# anemo2.net
KiCad netlist of a schematic drawn in EAGLE
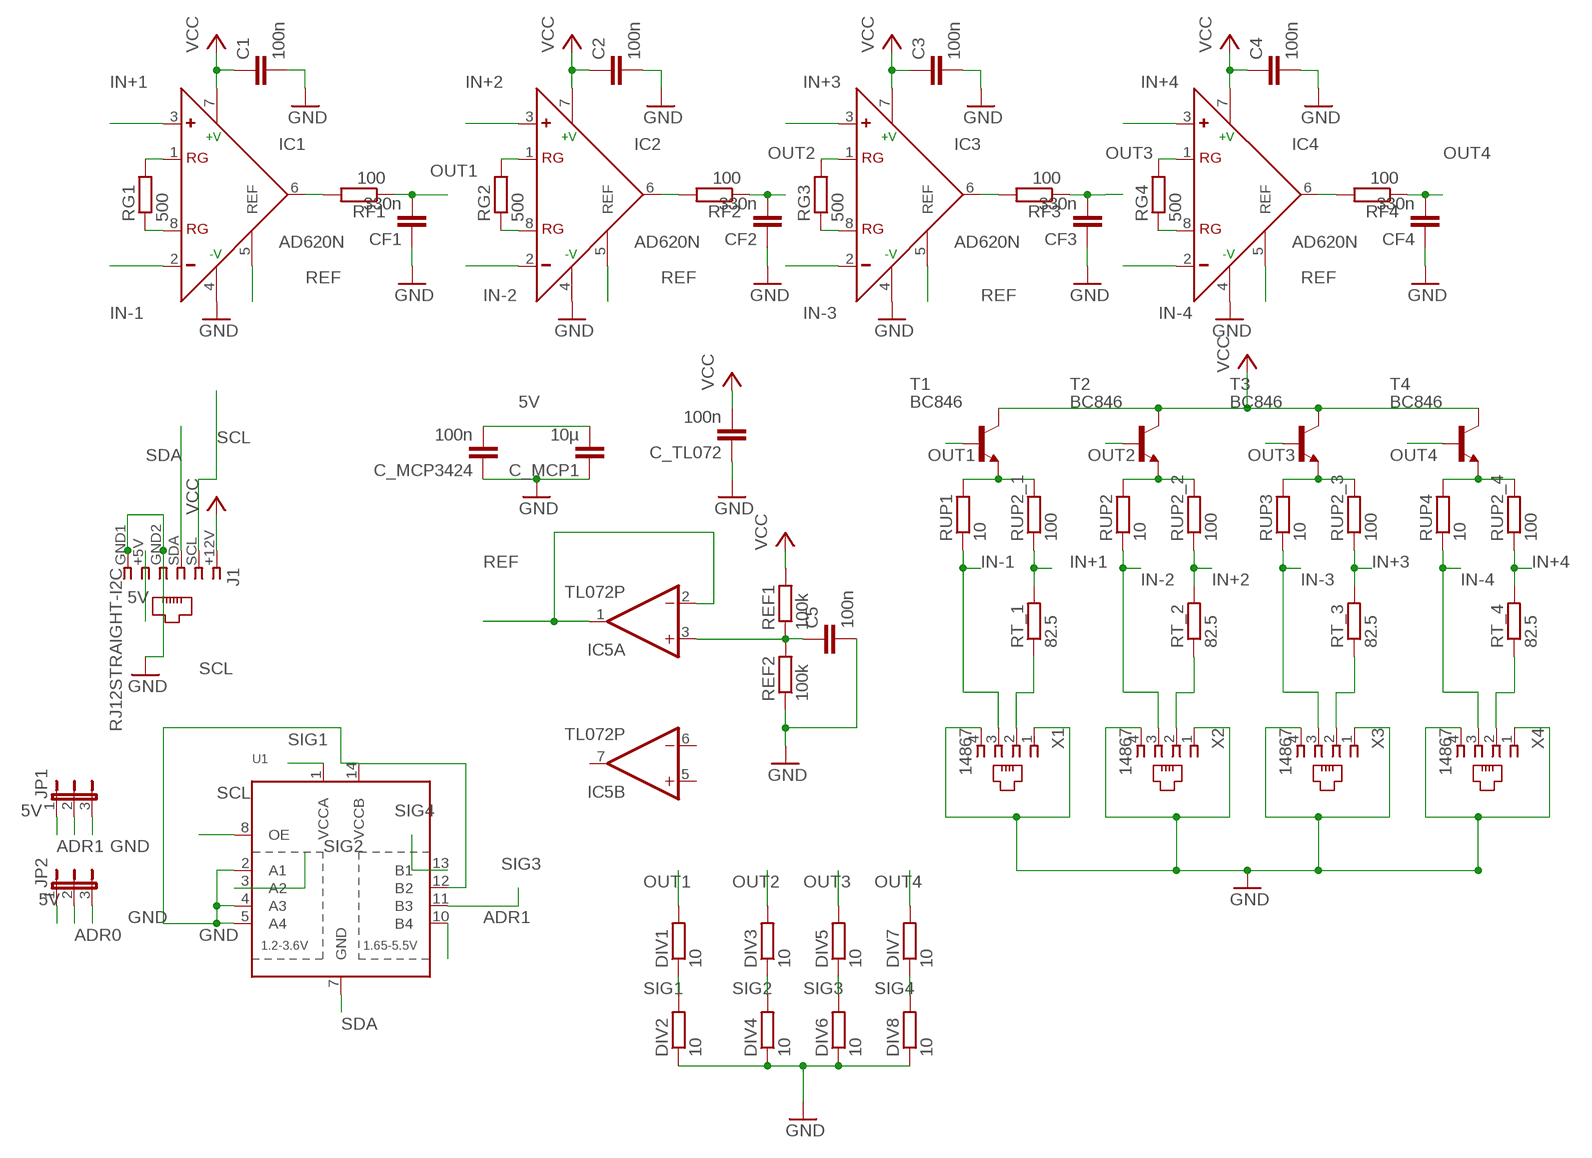
[diagram p0: schematic, sheet 1]

(export (version "E")
  (design (tool "Eeschema 10.0.6"))
  (components
    (comp (ref "C1")
      (value "100n")
      (footprint "eagle-import:C1206")
      (libsource (lib "eagle-import") (part "C-EUC1206"))
    )
    (comp (ref "C2")
      (value "100n")
      (footprint "eagle-import:C1206")
      (libsource (lib "eagle-import") (part "C-EUC1206"))
    )
    (comp (ref "C3")
      (value "100n")
      (footprint "eagle-import:C1206")
      (libsource (lib "eagle-import") (part "C-EUC1206"))
    )
    (comp (ref "C4")
      (value "100n")
      (footprint "eagle-import:C1206")
      (libsource (lib "eagle-import") (part "C-EUC1206"))
    )
    (comp (ref "C5")
      (value "100n")
      (footprint "eagle-import:C1206")
      (libsource (lib "eagle-import") (part "C-EUC1206"))
    )
    (comp (ref "CF1")
      (value "330n")
      (footprint "eagle-import:C1206")
      (libsource (lib "eagle-import") (part "C-EUC1206"))
    )
    (comp (ref "CF2")
      (value "330n")
      (footprint "eagle-import:C1206")
      (libsource (lib "eagle-import") (part "C-EUC1206"))
    )
    (comp (ref "CF3")
      (value "330n")
      (footprint "eagle-import:C1206")
      (libsource (lib "eagle-import") (part "C-EUC1206"))
    )
    (comp (ref "CF4")
      (value "330n")
      (footprint "eagle-import:C1206")
      (libsource (lib "eagle-import") (part "C-EUC1206"))
    )
    (comp (ref "C_MCP1")
      (value "10µ")
      (footprint "eagle-import:C1206")
      (libsource (lib "eagle-import") (part "C-EUC1206"))
    )
    (comp (ref "C_MCP3424")
      (value "100n")
      (footprint "eagle-import:C1206")
      (libsource (lib "eagle-import") (part "C-EUC1206"))
    )
    (comp (ref "C_TL072")
      (value "100n")
      (footprint "eagle-import:C1206")
      (libsource (lib "eagle-import") (part "C-EUC1206"))
    )
    (comp (ref "DIV1")
      (value "10")
      (footprint "eagle-import:M1206")
      (libsource (lib "eagle-import") (part "R-EU_M1206"))
    )
    (comp (ref "DIV2")
      (value "10")
      (footprint "eagle-import:M1206")
      (libsource (lib "eagle-import") (part "R-EU_M1206"))
    )
    (comp (ref "DIV3")
      (value "10")
      (footprint "eagle-import:M1206")
      (libsource (lib "eagle-import") (part "R-EU_M1206"))
    )
    (comp (ref "DIV4")
      (value "10")
      (footprint "eagle-import:M1206")
      (libsource (lib "eagle-import") (part "R-EU_M1206"))
    )
    (comp (ref "DIV5")
      (value "10")
      (footprint "eagle-import:M1206")
      (libsource (lib "eagle-import") (part "R-EU_M1206"))
    )
    (comp (ref "DIV6")
      (value "10")
      (footprint "eagle-import:M1206")
      (libsource (lib "eagle-import") (part "R-EU_M1206"))
    )
    (comp (ref "DIV7")
      (value "10")
      (footprint "eagle-import:M1206")
      (libsource (lib "eagle-import") (part "R-EU_M1206"))
    )
    (comp (ref "DIV8")
      (value "10")
      (footprint "eagle-import:M1206")
      (libsource (lib "eagle-import") (part "R-EU_M1206"))
    )
    (comp (ref "IC1")
      (value "AD620N")
      (footprint "eagle-import:DIL08")
      (fields (field (name "MF") "ALTERA CORPORATION") (field (name "MPN") "AD620AN"))
      (libsource (lib "eagle-import") (part "AD620N"))
    )
    (comp (ref "IC2")
      (value "AD620N")
      (footprint "eagle-import:DIL08")
      (fields (field (name "MF") "ALTERA CORPORATION") (field (name "MPN") "AD620AN"))
      (libsource (lib "eagle-import") (part "AD620N"))
    )
    (comp (ref "IC3")
      (value "AD620N")
      (footprint "eagle-import:DIL08")
      (fields (field (name "MF") "ALTERA CORPORATION") (field (name "MPN") "AD620AN"))
      (libsource (lib "eagle-import") (part "AD620N"))
    )
    (comp (ref "IC4")
      (value "AD620N")
      (footprint "eagle-import:DIL08")
      (fields (field (name "MF") "ALTERA CORPORATION") (field (name "MPN") "AD620AN"))
      (libsource (lib "eagle-import") (part "AD620N"))
    )
    (comp (ref "IC5")
      (value "TL072P")
      (footprint "eagle-import:DIL08")
      (libsource (lib "eagle-import") (part "TL072P"))
    )
    (comp (ref "J1")
      (value "RJ12STRAIGHT-I2C")
      (footprint "eagle-import:RJ12-STRAIGHT-I2C")
      (libsource (lib "eagle-import") (part "RJ12STRAIGHT-I2C"))
    )
    (comp (ref "JP1")
      (value "JP2E")
      (footprint "eagle-import:JP2")
      (libsource (lib "eagle-import") (part "JP2E"))
    )
    (comp (ref "JP2")
      (value "JP2E")
      (footprint "eagle-import:JP2")
      (libsource (lib "eagle-import") (part "JP2E"))
    )
    (comp (ref "REF1")
      (value "100k")
      (footprint "eagle-import:M1206")
      (libsource (lib "eagle-import") (part "R-EU_M1206"))
    )
    (comp (ref "REF2")
      (value "100k")
      (footprint "eagle-import:M1206")
      (libsource (lib "eagle-import") (part "R-EU_M1206"))
    )
    (comp (ref "RF1")
      (value "100")
      (footprint "eagle-import:M1206")
      (libsource (lib "eagle-import") (part "R-EU_M1206"))
    )
    (comp (ref "RF2")
      (value "100")
      (footprint "eagle-import:M1206")
      (libsource (lib "eagle-import") (part "R-EU_M1206"))
    )
    (comp (ref "RF3")
      (value "100")
      (footprint "eagle-import:M1206")
      (libsource (lib "eagle-import") (part "R-EU_M1206"))
    )
    (comp (ref "RF4")
      (value "100")
      (footprint "eagle-import:M1206")
      (libsource (lib "eagle-import") (part "R-EU_M1206"))
    )
    (comp (ref "RG1")
      (value "500")
      (footprint "eagle-import:M1206")
      (libsource (lib "eagle-import") (part "R-EU_M1206"))
    )
    (comp (ref "RG2")
      (value "500")
      (footprint "eagle-import:M1206")
      (libsource (lib "eagle-import") (part "R-EU_M1206"))
    )
    (comp (ref "RG3")
      (value "500")
      (footprint "eagle-import:M1206")
      (libsource (lib "eagle-import") (part "R-EU_M1206"))
    )
    (comp (ref "RG4")
      (value "500")
      (footprint "eagle-import:M1206")
      (libsource (lib "eagle-import") (part "R-EU_M1206"))
    )
    (comp (ref "RT_1")
      (value "82.5")
      (footprint "eagle-import:M1206")
      (libsource (lib "eagle-import") (part "R-EU_M1206"))
    )
    (comp (ref "RT_2")
      (value "82.5")
      (footprint "eagle-import:M1206")
      (libsource (lib "eagle-import") (part "R-EU_M1206"))
    )
    (comp (ref "RT_3")
      (value "82.5")
      (footprint "eagle-import:M1206")
      (libsource (lib "eagle-import") (part "R-EU_M1206"))
    )
    (comp (ref "RT_4")
      (value "82.5")
      (footprint "eagle-import:M1206")
      (libsource (lib "eagle-import") (part "R-EU_M1206"))
    )
    (comp (ref "RUP1")
      (value "10")
      (footprint "eagle-import:M1206")
      (libsource (lib "eagle-import") (part "R-EU_M1206"))
    )
    (comp (ref "RUP2")
      (value "10")
      (footprint "eagle-import:M1206")
      (libsource (lib "eagle-import") (part "R-EU_M1206"))
    )
    (comp (ref "RUP2_1")
      (value "100")
      (footprint "eagle-import:M1206")
      (libsource (lib "eagle-import") (part "R-EU_M1206"))
    )
    (comp (ref "RUP2_2")
      (value "100")
      (footprint "eagle-import:M1206")
      (libsource (lib "eagle-import") (part "R-EU_M1206"))
    )
    (comp (ref "RUP2_3")
      (value "100")
      (footprint "eagle-import:M1206")
      (libsource (lib "eagle-import") (part "R-EU_M1206"))
    )
    (comp (ref "RUP2_4")
      (value "100")
      (footprint "eagle-import:M1206")
      (libsource (lib "eagle-import") (part "R-EU_M1206"))
    )
    (comp (ref "RUP3")
      (value "10")
      (footprint "eagle-import:M1206")
      (libsource (lib "eagle-import") (part "R-EU_M1206"))
    )
    (comp (ref "RUP4")
      (value "10")
      (footprint "eagle-import:M1206")
      (libsource (lib "eagle-import") (part "R-EU_M1206"))
    )
    (comp (ref "T1")
      (value "BC846")
      (footprint "eagle-import:SOT23")
      (libsource (lib "eagle-import") (part "BC846"))
    )
    (comp (ref "T2")
      (value "BC846")
      (footprint "eagle-import:SOT23")
      (libsource (lib "eagle-import") (part "BC846"))
    )
    (comp (ref "T3")
      (value "BC846")
      (footprint "eagle-import:SOT23")
      (libsource (lib "eagle-import") (part "BC846"))
    )
    (comp (ref "T4")
      (value "BC846")
      (footprint "eagle-import:SOT23")
      (libsource (lib "eagle-import") (part "BC846"))
    )
    (comp (ref "U1")
      (value "TXB0104PWRSOIC14")
      (footprint "eagle-import:SO14")
      (libsource (lib "eagle-import") (part "TXB0104PWRSOIC14"))
    )
    (comp (ref "X1")
      (value "14867")
      (footprint "eagle-import:14867")
      (libsource (lib "eagle-import") (part "14867"))
    )
    (comp (ref "X2")
      (value "14867")
      (footprint "eagle-import:14867")
      (libsource (lib "eagle-import") (part "14867"))
    )
    (comp (ref "X3")
      (value "14867")
      (footprint "eagle-import:14867")
      (libsource (lib "eagle-import") (part "14867"))
    )
    (comp (ref "X4")
      (value "14867")
      (footprint "eagle-import:14867")
      (libsource (lib "eagle-import") (part "14867"))
    )
  )
  (nets
    (net (code "1") (name "/5V") (class "Default")
      (node (ref "C_MCP1") (pin "2") (pinfunction "2_2") (pintype "passive"))
      (node (ref "C_MCP3424") (pin "2") (pinfunction "2_2") (pintype "passive"))
      (node (ref "J1") (pin "+5V") (pinfunction "5_+5V") (pintype "bidirectional"))
      (node (ref "JP1") (pin "1") (pinfunction "1_1") (pintype "passive"))
      (node (ref "JP2") (pin "1") (pinfunction "1_1") (pintype "passive"))
    )
    (net (code "2") (name "/ADR0") (class "Default")
      (node (ref "JP2") (pin "2") (pinfunction "2_2") (pintype "passive"))
    )
    (net (code "3") (name "/ADR1") (class "Default")
      (node (ref "JP1") (pin "2") (pinfunction "2_2") (pintype "passive"))
      (node (ref "U1") (pin "10") (pinfunction "B4_10") (pintype "bidirectional"))
    )
    (net (code "4") (name "/IN+1") (class "Default")
      (node (ref "IC1") (pin "3") (pinfunction "+_3") (pintype "input"))
      (node (ref "RT_1") (pin "2") (pinfunction "2_2") (pintype "passive"))
      (node (ref "RUP2_1") (pin "1") (pinfunction "1_1") (pintype "passive"))
    )
    (net (code "5") (name "/IN+2") (class "Default")
      (node (ref "IC2") (pin "3") (pinfunction "+_3") (pintype "input"))
      (node (ref "RT_2") (pin "2") (pinfunction "2_2") (pintype "passive"))
      (node (ref "RUP2_2") (pin "1") (pinfunction "1_1") (pintype "passive"))
    )
    (net (code "6") (name "/IN+3") (class "Default")
      (node (ref "IC3") (pin "3") (pinfunction "+_3") (pintype "input"))
      (node (ref "RT_3") (pin "2") (pinfunction "2_2") (pintype "passive"))
      (node (ref "RUP2_3") (pin "1") (pinfunction "1_1") (pintype "passive"))
    )
    (net (code "7") (name "/IN+4") (class "Default")
      (node (ref "IC4") (pin "3") (pinfunction "+_3") (pintype "input"))
      (node (ref "RT_4") (pin "2") (pinfunction "2_2") (pintype "passive"))
      (node (ref "RUP2_4") (pin "1") (pinfunction "1_1") (pintype "passive"))
    )
    (net (code "8") (name "/IN-1") (class "Default")
      (node (ref "IC1") (pin "2") (pinfunction "-_2") (pintype "input"))
      (node (ref "RUP1") (pin "1") (pinfunction "1_1") (pintype "passive"))
      (node (ref "X1") (pin "3") (pinfunction "3_3") (pintype "passive"))
    )
    (net (code "9") (name "/IN-2") (class "Default")
      (node (ref "IC2") (pin "2") (pinfunction "-_2") (pintype "input"))
      (node (ref "RUP2") (pin "1") (pinfunction "1_1") (pintype "passive"))
      (node (ref "X2") (pin "3") (pinfunction "3_3") (pintype "passive"))
    )
    (net (code "10") (name "/IN-3") (class "Default")
      (node (ref "IC3") (pin "2") (pinfunction "-_2") (pintype "input"))
      (node (ref "RUP3") (pin "1") (pinfunction "1_1") (pintype "passive"))
      (node (ref "X3") (pin "3") (pinfunction "3_3") (pintype "passive"))
    )
    (net (code "11") (name "/IN-4") (class "Default")
      (node (ref "IC4") (pin "2") (pinfunction "-_2") (pintype "input"))
      (node (ref "RUP4") (pin "1") (pinfunction "1_1") (pintype "passive"))
      (node (ref "X4") (pin "3") (pinfunction "3_3") (pintype "passive"))
    )
    (net (code "12") (name "/OUT1") (class "Default")
      (node (ref "CF1") (pin "2") (pinfunction "2_2") (pintype "passive"))
      (node (ref "DIV1") (pin "2") (pinfunction "2_2") (pintype "passive"))
      (node (ref "RF1") (pin "1") (pinfunction "1_1") (pintype "passive"))
      (node (ref "T1") (pin "1") (pinfunction "B_1") (pintype "passive"))
    )
    (net (code "13") (name "/OUT2") (class "Default")
      (node (ref "CF2") (pin "2") (pinfunction "2_2") (pintype "passive"))
      (node (ref "DIV3") (pin "2") (pinfunction "2_2") (pintype "passive"))
      (node (ref "RF2") (pin "1") (pinfunction "1_1") (pintype "passive"))
      (node (ref "T2") (pin "1") (pinfunction "B_1") (pintype "passive"))
    )
    (net (code "14") (name "/OUT3") (class "Default")
      (node (ref "CF3") (pin "2") (pinfunction "2_2") (pintype "passive"))
      (node (ref "DIV5") (pin "2") (pinfunction "2_2") (pintype "passive"))
      (node (ref "RF3") (pin "1") (pinfunction "1_1") (pintype "passive"))
      (node (ref "T3") (pin "1") (pinfunction "B_1") (pintype "passive"))
    )
    (net (code "15") (name "/OUT4") (class "Default")
      (node (ref "CF4") (pin "2") (pinfunction "2_2") (pintype "passive"))
      (node (ref "DIV7") (pin "2") (pinfunction "2_2") (pintype "passive"))
      (node (ref "RF4") (pin "1") (pinfunction "1_1") (pintype "passive"))
      (node (ref "T4") (pin "1") (pinfunction "B_1") (pintype "passive"))
    )
    (net (code "16") (name "/REF") (class "Default")
      (node (ref "IC1") (pin "5") (pinfunction "REF_5") (pintype "passive"))
      (node (ref "IC2") (pin "5") (pinfunction "REF_5") (pintype "passive"))
      (node (ref "IC3") (pin "5") (pinfunction "REF_5") (pintype "passive"))
      (node (ref "IC4") (pin "5") (pinfunction "REF_5") (pintype "passive"))
      (node (ref "IC5") (pin "1") (pinfunction "OUT_1") (pintype "output"))
      (node (ref "IC5") (pin "2") (pinfunction "-IN_2") (pintype "input"))
    )
    (net (code "17") (name "/SCL") (class "Default")
      (node (ref "J1") (pin "SCL") (pinfunction "2_SCL") (pintype "bidirectional"))
      (node (ref "U1") (pin "8") (pinfunction "OE_8") (pintype "bidirectional"))
    )
    (net (code "18") (name "/SDA") (class "Default")
      (node (ref "J1") (pin "SDA") (pinfunction "3_SDA") (pintype "bidirectional"))
      (node (ref "U1") (pin "7") (pinfunction "GND_7") (pintype "bidirectional"))
    )
    (net (code "19") (name "/SIG1") (class "Default")
      (node (ref "DIV1") (pin "1") (pinfunction "1_1") (pintype "passive"))
      (node (ref "DIV2") (pin "2") (pinfunction "2_2") (pintype "passive"))
      (node (ref "U1") (pin "1") (pinfunction "VCCA_1") (pintype "bidirectional"))
    )
    (net (code "20") (name "/SIG2") (class "Default")
      (node (ref "DIV3") (pin "1") (pinfunction "1_1") (pintype "passive"))
      (node (ref "DIV4") (pin "2") (pinfunction "2_2") (pintype "passive"))
      (node (ref "U1") (pin "3") (pinfunction "A2_3") (pintype "bidirectional"))
    )
    (net (code "21") (name "/SIG3") (class "Default")
      (node (ref "DIV5") (pin "1") (pinfunction "1_1") (pintype "passive"))
      (node (ref "DIV6") (pin "2") (pinfunction "2_2") (pintype "passive"))
      (node (ref "U1") (pin "11") (pinfunction "B3_11") (pintype "bidirectional"))
    )
    (net (code "22") (name "/SIG4") (class "Default")
      (node (ref "DIV7") (pin "1") (pinfunction "1_1") (pintype "passive"))
      (node (ref "DIV8") (pin "2") (pinfunction "2_2") (pintype "passive"))
      (node (ref "U1") (pin "13") (pinfunction "B1_13") (pintype "bidirectional"))
    )
    (net (code "23") (name "GND") (class "Default")
      (node (ref "C1") (pin "2") (pinfunction "2_2") (pintype "passive"))
      (node (ref "C2") (pin "2") (pinfunction "2_2") (pintype "passive"))
      (node (ref "C3") (pin "2") (pinfunction "2_2") (pintype "passive"))
      (node (ref "C4") (pin "2") (pinfunction "2_2") (pintype "passive"))
      (node (ref "C5") (pin "2") (pinfunction "2_2") (pintype "passive"))
      (node (ref "CF1") (pin "1") (pinfunction "1_1") (pintype "passive"))
      (node (ref "CF2") (pin "1") (pinfunction "1_1") (pintype "passive"))
      (node (ref "CF3") (pin "1") (pinfunction "1_1") (pintype "passive"))
      (node (ref "CF4") (pin "1") (pinfunction "1_1") (pintype "passive"))
      (node (ref "C_MCP1") (pin "1") (pinfunction "1_1") (pintype "passive"))
      (node (ref "C_MCP3424") (pin "1") (pinfunction "1_1") (pintype "passive"))
      (node (ref "C_TL072") (pin "1") (pinfunction "1_1") (pintype "passive"))
      (node (ref "DIV2") (pin "1") (pinfunction "1_1") (pintype "passive"))
      (node (ref "DIV4") (pin "1") (pinfunction "1_1") (pintype "passive"))
      (node (ref "DIV6") (pin "1") (pinfunction "1_1") (pintype "passive"))
      (node (ref "DIV8") (pin "1") (pinfunction "1_1") (pintype "passive"))
      (node (ref "IC1") (pin "4") (pinfunction "-V_4") (pintype "power_in"))
      (node (ref "IC2") (pin "4") (pinfunction "-V_4") (pintype "power_in"))
      (node (ref "IC3") (pin "4") (pinfunction "-V_4") (pintype "power_in"))
      (node (ref "IC4") (pin "4") (pinfunction "-V_4") (pintype "power_in"))
      (node (ref "J1") (pin "GND1") (pinfunction "6_GND1") (pintype "bidirectional"))
      (node (ref "J1") (pin "GND2") (pinfunction "4_GND2") (pintype "bidirectional"))
      (node (ref "JP1") (pin "3") (pinfunction "3_3") (pintype "passive"))
      (node (ref "JP2") (pin "3") (pinfunction "3_3") (pintype "passive"))
      (node (ref "REF2") (pin "1") (pinfunction "1_1") (pintype "passive"))
      (node (ref "U1") (pin "12") (pinfunction "B2_12") (pintype "bidirectional"))
      (node (ref "U1") (pin "14") (pinfunction "VCCB_14") (pintype "bidirectional"))
      (node (ref "U1") (pin "2") (pinfunction "A1_2") (pintype "bidirectional"))
      (node (ref "U1") (pin "4") (pinfunction "A3_4") (pintype "bidirectional"))
      (node (ref "U1") (pin "5") (pinfunction "A4_5") (pintype "bidirectional"))
      (node (ref "X1") (pin "1") (pinfunction "1_1") (pintype "passive"))
      (node (ref "X1") (pin "4") (pinfunction "4_4") (pintype "passive"))
      (node (ref "X2") (pin "1") (pinfunction "1_1") (pintype "passive"))
      (node (ref "X2") (pin "4") (pinfunction "4_4") (pintype "passive"))
      (node (ref "X3") (pin "1") (pinfunction "1_1") (pintype "passive"))
      (node (ref "X3") (pin "4") (pinfunction "4_4") (pintype "passive"))
      (node (ref "X4") (pin "1") (pinfunction "1_1") (pintype "passive"))
      (node (ref "X4") (pin "4") (pinfunction "4_4") (pintype "passive"))
    )
    (net (code "24") (name "Net-(IC1-OUT)") (class "Default")
      (node (ref "IC1") (pin "6") (pinfunction "OUT_6") (pintype "output"))
      (node (ref "RF1") (pin "2") (pinfunction "2_2") (pintype "passive"))
    )
    (net (code "25") (name "Net-(IC1-RG-Pad1)") (class "Default")
      (node (ref "IC1") (pin "1") (pinfunction "RG_1") (pintype "passive"))
      (node (ref "RG1") (pin "2") (pinfunction "2_2") (pintype "passive"))
    )
    (net (code "26") (name "Net-(IC1-RG-Pad8)") (class "Default")
      (node (ref "IC1") (pin "8") (pinfunction "RG_8") (pintype "passive"))
      (node (ref "RG1") (pin "1") (pinfunction "1_1") (pintype "passive"))
    )
    (net (code "27") (name "Net-(IC2-OUT)") (class "Default")
      (node (ref "IC2") (pin "6") (pinfunction "OUT_6") (pintype "output"))
      (node (ref "RF2") (pin "2") (pinfunction "2_2") (pintype "passive"))
    )
    (net (code "28") (name "Net-(IC2-RG-Pad1)") (class "Default")
      (node (ref "IC2") (pin "1") (pinfunction "RG_1") (pintype "passive"))
      (node (ref "RG2") (pin "2") (pinfunction "2_2") (pintype "passive"))
    )
    (net (code "29") (name "Net-(IC2-RG-Pad8)") (class "Default")
      (node (ref "IC2") (pin "8") (pinfunction "RG_8") (pintype "passive"))
      (node (ref "RG2") (pin "1") (pinfunction "1_1") (pintype "passive"))
    )
    (net (code "30") (name "Net-(IC3-OUT)") (class "Default")
      (node (ref "IC3") (pin "6") (pinfunction "OUT_6") (pintype "output"))
      (node (ref "RF3") (pin "2") (pinfunction "2_2") (pintype "passive"))
    )
    (net (code "31") (name "Net-(IC3-RG-Pad1)") (class "Default")
      (node (ref "IC3") (pin "1") (pinfunction "RG_1") (pintype "passive"))
      (node (ref "RG3") (pin "2") (pinfunction "2_2") (pintype "passive"))
    )
    (net (code "32") (name "Net-(IC3-RG-Pad8)") (class "Default")
      (node (ref "IC3") (pin "8") (pinfunction "RG_8") (pintype "passive"))
      (node (ref "RG3") (pin "1") (pinfunction "1_1") (pintype "passive"))
    )
    (net (code "33") (name "Net-(IC4-OUT)") (class "Default")
      (node (ref "IC4") (pin "6") (pinfunction "OUT_6") (pintype "output"))
      (node (ref "RF4") (pin "2") (pinfunction "2_2") (pintype "passive"))
    )
    (net (code "34") (name "Net-(IC4-RG-Pad1)") (class "Default")
      (node (ref "IC4") (pin "1") (pinfunction "RG_1") (pintype "passive"))
      (node (ref "RG4") (pin "2") (pinfunction "2_2") (pintype "passive"))
    )
    (net (code "35") (name "Net-(IC4-RG-Pad8)") (class "Default")
      (node (ref "IC4") (pin "8") (pinfunction "RG_8") (pintype "passive"))
      (node (ref "RG4") (pin "1") (pinfunction "1_1") (pintype "passive"))
    )
    (net (code "36") (name "Net-(IC5A-+IN)") (class "Default")
      (node (ref "C5") (pin "1") (pinfunction "1_1") (pintype "passive"))
      (node (ref "IC5") (pin "3") (pinfunction "+IN_3") (pintype "input"))
      (node (ref "REF1") (pin "1") (pinfunction "1_1") (pintype "passive"))
      (node (ref "REF2") (pin "2") (pinfunction "2_2") (pintype "passive"))
    )
    (net (code "37") (name "Net-(RT_1-Pad1)") (class "Default")
      (node (ref "RT_1") (pin "1") (pinfunction "1_1") (pintype "passive"))
      (node (ref "X1") (pin "2") (pinfunction "2_2") (pintype "passive"))
    )
    (net (code "38") (name "Net-(RT_2-Pad1)") (class "Default")
      (node (ref "RT_2") (pin "1") (pinfunction "1_1") (pintype "passive"))
      (node (ref "X2") (pin "2") (pinfunction "2_2") (pintype "passive"))
    )
    (net (code "39") (name "Net-(RT_3-Pad1)") (class "Default")
      (node (ref "RT_3") (pin "1") (pinfunction "1_1") (pintype "passive"))
      (node (ref "X3") (pin "2") (pinfunction "2_2") (pintype "passive"))
    )
    (net (code "40") (name "Net-(RT_4-Pad1)") (class "Default")
      (node (ref "RT_4") (pin "1") (pinfunction "1_1") (pintype "passive"))
      (node (ref "X4") (pin "2") (pinfunction "2_2") (pintype "passive"))
    )
    (net (code "41") (name "Net-(T1-E)") (class "Default")
      (node (ref "RUP1") (pin "2") (pinfunction "2_2") (pintype "passive"))
      (node (ref "RUP2_1") (pin "2") (pinfunction "2_2") (pintype "passive"))
      (node (ref "T1") (pin "2") (pinfunction "E_2") (pintype "passive"))
    )
    (net (code "42") (name "Net-(T2-E)") (class "Default")
      (node (ref "RUP2") (pin "2") (pinfunction "2_2") (pintype "passive"))
      (node (ref "RUP2_2") (pin "2") (pinfunction "2_2") (pintype "passive"))
      (node (ref "T2") (pin "2") (pinfunction "E_2") (pintype "passive"))
    )
    (net (code "43") (name "Net-(T3-E)") (class "Default")
      (node (ref "RUP2_3") (pin "2") (pinfunction "2_2") (pintype "passive"))
      (node (ref "RUP3") (pin "2") (pinfunction "2_2") (pintype "passive"))
      (node (ref "T3") (pin "2") (pinfunction "E_2") (pintype "passive"))
    )
    (net (code "44") (name "Net-(T4-E)") (class "Default")
      (node (ref "RUP2_4") (pin "2") (pinfunction "2_2") (pintype "passive"))
      (node (ref "RUP4") (pin "2") (pinfunction "2_2") (pintype "passive"))
      (node (ref "T4") (pin "2") (pinfunction "E_2") (pintype "passive"))
    )
    (net (code "45") (name "VCC") (class "Default")
      (node (ref "C1") (pin "1") (pinfunction "1_1") (pintype "passive"))
      (node (ref "C2") (pin "1") (pinfunction "1_1") (pintype "passive"))
      (node (ref "C3") (pin "1") (pinfunction "1_1") (pintype "passive"))
      (node (ref "C4") (pin "1") (pinfunction "1_1") (pintype "passive"))
      (node (ref "C_TL072") (pin "2") (pinfunction "2_2") (pintype "passive"))
      (node (ref "IC1") (pin "7") (pinfunction "+V_7") (pintype "power_in"))
      (node (ref "IC2") (pin "7") (pinfunction "+V_7") (pintype "power_in"))
      (node (ref "IC3") (pin "7") (pinfunction "+V_7") (pintype "power_in"))
      (node (ref "IC4") (pin "7") (pinfunction "+V_7") (pintype "power_in"))
      (node (ref "J1") (pin "+12V") (pinfunction "1_+12V") (pintype "bidirectional"))
      (node (ref "REF1") (pin "2") (pinfunction "2_2") (pintype "passive"))
      (node (ref "T1") (pin "3") (pinfunction "C_3") (pintype "passive"))
      (node (ref "T2") (pin "3") (pinfunction "C_3") (pintype "passive"))
      (node (ref "T3") (pin "3") (pinfunction "C_3") (pintype "passive"))
      (node (ref "T4") (pin "3") (pinfunction "C_3") (pintype "passive"))
    )
    (net (code "46") (name "unconnected-(IC5B-+IN-Pad5)") (class "Default")
      (node (ref "IC5") (pin "5") (pinfunction "+IN_5") (pintype "input"))
    )
    (net (code "47") (name "unconnected-(IC5B--IN-Pad6)") (class "Default")
      (node (ref "IC5") (pin "6") (pinfunction "-IN_6") (pintype "input"))
    )
    (net (code "48") (name "unconnected-(IC5B-OUT-Pad7)") (class "Default")
      (node (ref "IC5") (pin "7") (pinfunction "OUT_7") (pintype "output"))
    )
  )
)
